# Selecteur.net
KiCad netlist of a schematic drawn in Altium Designer
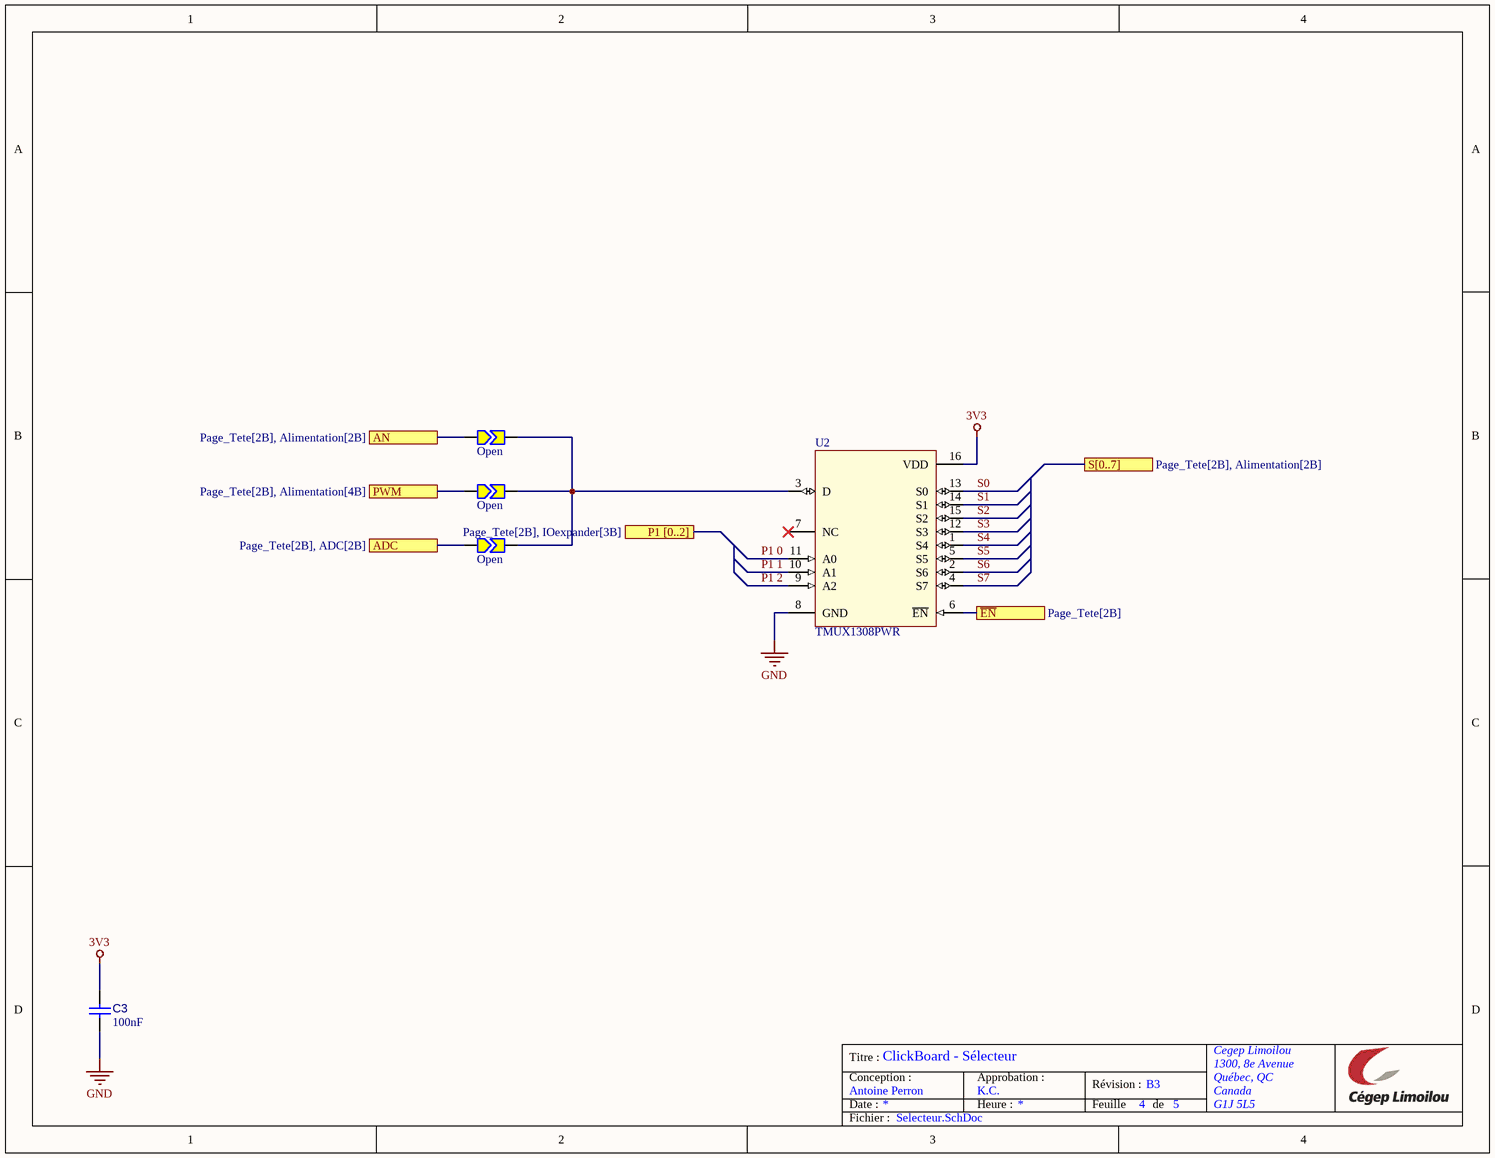
[diagram p0: Selecteur.SchDoc]

(export (version "E")
  (design (tool "Eeschema 10.0.6"))
  (components
    (comp (ref "C3")
      (value "100nF")
      (footprint "C_1608[0603]")
      (description "Capacitor type 1")
      (fields (field (name "TOLERANCE") "10%") (field (name "Comment") "CAP CER 100nF 50V 0603"))
      (libsource (lib "TEP-AltiumLib-Passives-RLC") (part "capacitor"))
    )
    (comp (ref "SB1")
      (value "Open")
      (footprint "SB-TINY-OPEN")
      (description "Solder Jumper")
      (libsource (lib "TEP-AltiumLib-Hardware") (part "Solder-Jumper-Open"))
    )
    (comp (ref "SB2")
      (value "Open")
      (footprint "SB-TINY-OPEN")
      (description "Solder Jumper")
      (libsource (lib "TEP-AltiumLib-Hardware") (part "Solder-Jumper-Open"))
    )
    (comp (ref "SB3")
      (value "Open")
      (footprint "SB-TINY-OPEN")
      (description "Solder Jumper")
      (libsource (lib "TEP-AltiumLib-Hardware") (part "Solder-Jumper-Open"))
    )
    (comp (ref "U2")
      (value "TMUX1308PWR")
      (footprint "U_TSSOP65P500X450-16")
      (description "IC MUX 8:1 195OHM 16TSSOP")
      (libsource (lib "TEP-AltiumLib-ICs") (part "U_TMUX1308PWR"))
    )
  )
  (nets
    (net (code "1") (name "/ADC") (class "Default")
      (node (ref "SB3") (pin "1") (pinfunction "1_1") (pintype "passive"))
    )
    (net (code "2") (name "/AN") (class "Default")
      (node (ref "SB1") (pin "1") (pinfunction "1_1") (pintype "passive"))
    )
    (net (code "3") (name "/P1 0") (class "Default")
      (node (ref "U2") (pin "11") (pinfunction "A0_11") (pintype "input"))
    )
    (net (code "4") (name "/P1 1") (class "Default")
      (node (ref "U2") (pin "10") (pinfunction "A1_10") (pintype "input"))
    )
    (net (code "5") (name "/P1 2") (class "Default")
      (node (ref "U2") (pin "9") (pinfunction "A2_9") (pintype "input"))
    )
    (net (code "7") (name "/PWM") (class "Default")
      (node (ref "SB2") (pin "1") (pinfunction "1_1") (pintype "passive"))
    )
    (net (code "8") (name "/S0") (class "Default")
      (node (ref "U2") (pin "13") (pinfunction "S0_13") (pintype "bidirectional"))
    )
    (net (code "9") (name "/S1") (class "Default")
      (node (ref "U2") (pin "14") (pinfunction "S1_14") (pintype "bidirectional"))
    )
    (net (code "10") (name "/S2") (class "Default")
      (node (ref "U2") (pin "15") (pinfunction "S2_15") (pintype "bidirectional"))
    )
    (net (code "11") (name "/S3") (class "Default")
      (node (ref "U2") (pin "12") (pinfunction "S3_12") (pintype "bidirectional"))
    )
    (net (code "12") (name "/S4") (class "Default")
      (node (ref "U2") (pin "1") (pinfunction "S4_1") (pintype "bidirectional"))
    )
    (net (code "13") (name "/S5") (class "Default")
      (node (ref "U2") (pin "5") (pinfunction "S5_5") (pintype "bidirectional"))
    )
    (net (code "14") (name "/S6") (class "Default")
      (node (ref "U2") (pin "2") (pinfunction "S6_2") (pintype "bidirectional"))
    )
    (net (code "15") (name "/S7") (class "Default")
      (node (ref "U2") (pin "4") (pinfunction "S7_4") (pintype "bidirectional"))
    )
    (net (code "17") (name "/~{EN}") (class "Default")
      (node (ref "U2") (pin "6") (pinfunction "~{EN}_6") (pintype "input"))
    )
    (net (code "18") (name "3V3") (class "Default")
      (node (ref "C3") (pin "2") (pinfunction "2_2") (pintype "passive"))
      (node (ref "U2") (pin "16") (pinfunction "VDD_16") (pintype "power_in"))
    )
    (net (code "19") (name "GND") (class "Default")
      (node (ref "C3") (pin "1") (pinfunction "1_1") (pintype "passive"))
      (node (ref "U2") (pin "8") (pinfunction "GND_8") (pintype "power_in"))
    )
    (net (code "20") (name "Net-(U2-D)") (class "Default")
      (node (ref "SB1") (pin "2") (pinfunction "2_2") (pintype "passive"))
      (node (ref "SB2") (pin "2") (pinfunction "2_2") (pintype "passive"))
      (node (ref "SB3") (pin "2") (pinfunction "2_2") (pintype "passive"))
      (node (ref "U2") (pin "3") (pinfunction "D_3") (pintype "bidirectional"))
    )
    (net (code "21") (name "unconnected-(U2-NC-Pad7)") (class "Default")
      (node (ref "U2") (pin "7") (pinfunction "NC_7") (pintype "passive+no_connect"))
    )
  )
)
